# integradorleg.net
KiCad netlist of a schematic drawn in Altium Designer
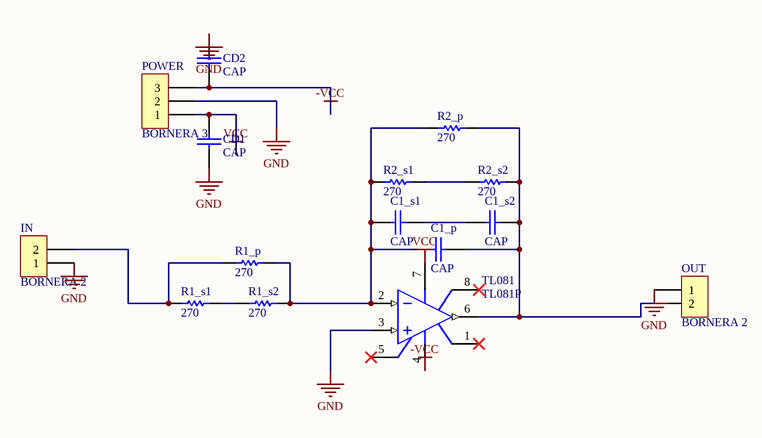
[diagram p0: integradorleg.SchDoc]

(export (version "E")
  (design (tool "Eeschema 10.0.6"))
  (components
    (comp (ref "C1_p") (value "CAP") (footprint "0805") (libsource (lib "LIBEBAL") (part "CAP")))
    (comp (ref "C1_s1") (value "CAP") (footprint "0805") (libsource (lib "LIBEBAL") (part "CAP")))
    (comp (ref "C1_s2") (value "CAP") (footprint "0805") (libsource (lib "LIBEBAL") (part "CAP")))
    (comp (ref "CD1") (value "CAP") (footprint "0805") (libsource (lib "LIBEBAL") (part "CAP")))
    (comp (ref "CD2") (value "CAP") (footprint "0805") (libsource (lib "LIBEBAL") (part "CAP")))
    (comp (ref "IN") (value "BORNERA 2") (footprint "BORNERA2") (libsource (lib "") (part "BORNERA 2_1")))
    (comp (ref "OUT")
      (value "BORNERA 2")
      (footprint "BORNERA2")
      (libsource (lib "LIB PIO IX") (part "BORNERA 2"))
    )
    (comp (ref "POWER")
      (value "BORNERA 3")
      (footprint "BORNERA3")
      (libsource (lib "LIB PIO IX") (part "BORNERA 3"))
    )
    (comp (ref "R1_p") (value "270") (footprint "0805") (libsource (lib "LIB PIO IX") (part "RES")))
    (comp (ref "R1_s1") (value "270") (footprint "0805") (libsource (lib "LIB PIO IX") (part "RES")))
    (comp (ref "R1_s2") (value "270") (footprint "0805") (libsource (lib "LIB PIO IX") (part "RES")))
    (comp (ref "R2_p") (value "270") (footprint "0805") (libsource (lib "LIB PIO IX") (part "RES")))
    (comp (ref "R2_s1") (value "270") (footprint "0805") (libsource (lib "LIB PIO IX") (part "RES")))
    (comp (ref "R2_s2") (value "270") (footprint "0805") (libsource (lib "LIB PIO IX") (part "RES")))
    (comp (ref "TL081")
      (value "TL081P")
      (footprint "P008")
      (description "JFET-Input Operational Amplifier")
      (fields (field (name "PUBLISHER") "Altium Limited"))
      (libsource (lib "TI Operational Amplifier") (part "TL081P"))
    )
  )
  (nets
    (net (code "1") (name "-VCC") (class "Default")
      (node (ref "CD2") (pin "2") (pinfunction "2_2") (pintype "passive"))
      (node (ref "POWER") (pin "3") (pinfunction "3_3") (pintype "passive"))
      (node (ref "TL081") (pin "4") (pinfunction "V-_4") (pintype "power_in"))
    )
    (net (code "2") (name "GND") (class "Default")
      (node (ref "CD1") (pin "2") (pinfunction "2_2") (pintype "passive"))
      (node (ref "CD2") (pin "1") (pinfunction "1_1") (pintype "passive"))
      (node (ref "IN") (pin "1") (pinfunction "1_1") (pintype "passive"))
      (node (ref "OUT") (pin "1") (pinfunction "1_1") (pintype "passive"))
      (node (ref "POWER") (pin "2") (pinfunction "2_2") (pintype "passive"))
      (node (ref "TL081") (pin "3") (pinfunction "IN+_3") (pintype "input"))
    )
    (net (code "3") (name "Net-(C1_s1-Pad2)") (class "Default")
      (node (ref "C1_s1") (pin "2") (pinfunction "2_2") (pintype "passive"))
      (node (ref "C1_s2") (pin "1") (pinfunction "1_1") (pintype "passive"))
    )
    (net (code "4") (name "Net-(IN-Pad2)") (class "Default")
      (node (ref "IN") (pin "2") (pinfunction "2_2") (pintype "passive"))
      (node (ref "R1_p") (pin "1") (pinfunction "1_1") (pintype "passive"))
      (node (ref "R1_s1") (pin "1") (pinfunction "1_1") (pintype "passive"))
    )
    (net (code "5") (name "Net-(R1_s1-Pad2)") (class "Default")
      (node (ref "R1_s1") (pin "2") (pinfunction "2_2") (pintype "passive"))
      (node (ref "R1_s2") (pin "1") (pinfunction "1_1") (pintype "passive"))
    )
    (net (code "6") (name "Net-(R2_s1-Pad2)") (class "Default")
      (node (ref "R2_s1") (pin "2") (pinfunction "2_2") (pintype "passive"))
      (node (ref "R2_s2") (pin "1") (pinfunction "1_1") (pintype "passive"))
    )
    (net (code "7") (name "Net-(TL081-IN-)") (class "Default")
      (node (ref "C1_p") (pin "1") (pinfunction "1_1") (pintype "passive"))
      (node (ref "C1_s1") (pin "1") (pinfunction "1_1") (pintype "passive"))
      (node (ref "R1_p") (pin "2") (pinfunction "2_2") (pintype "passive"))
      (node (ref "R1_s2") (pin "2") (pinfunction "2_2") (pintype "passive"))
      (node (ref "R2_p") (pin "1") (pinfunction "1_1") (pintype "passive"))
      (node (ref "R2_s1") (pin "1") (pinfunction "1_1") (pintype "passive"))
      (node (ref "TL081") (pin "2") (pinfunction "IN-_2") (pintype "input"))
    )
    (net (code "8") (name "Net-(TL081-OUT)") (class "Default")
      (node (ref "C1_p") (pin "2") (pinfunction "2_2") (pintype "passive"))
      (node (ref "C1_s2") (pin "2") (pinfunction "2_2") (pintype "passive"))
      (node (ref "OUT") (pin "2") (pinfunction "2_2") (pintype "passive"))
      (node (ref "R2_p") (pin "2") (pinfunction "2_2") (pintype "passive"))
      (node (ref "R2_s2") (pin "2") (pinfunction "2_2") (pintype "passive"))
      (node (ref "TL081") (pin "6") (pinfunction "OUT_6") (pintype "output"))
    )
    (net (code "9") (name "VCC") (class "Default")
      (node (ref "CD1") (pin "1") (pinfunction "1_1") (pintype "passive"))
      (node (ref "POWER") (pin "1") (pinfunction "1_1") (pintype "passive"))
      (node (ref "TL081") (pin "7") (pinfunction "V+_7") (pintype "power_in"))
    )
    (net (code "10") (name "unconnected-(TL081-NC-Pad8)") (class "Default")
      (node (ref "TL081") (pin "8") (pinfunction "NC_8") (pintype "passive+no_connect"))
    )
    (net (code "11") (name "unconnected-(TL081-OS_TRIM-Pad1)") (class "Default")
      (node (ref "TL081") (pin "1") (pinfunction "OS_TRIM_1") (pintype "passive+no_connect"))
    )
    (net (code "12") (name "unconnected-(TL081-OS_TRIM-Pad5)") (class "Default")
      (node (ref "TL081") (pin "5") (pinfunction "OS_TRIM_5") (pintype "passive+no_connect"))
    )
  )
)
